# 18650_Capacity.net
KiCad netlist of a schematic drawn in EAGLE
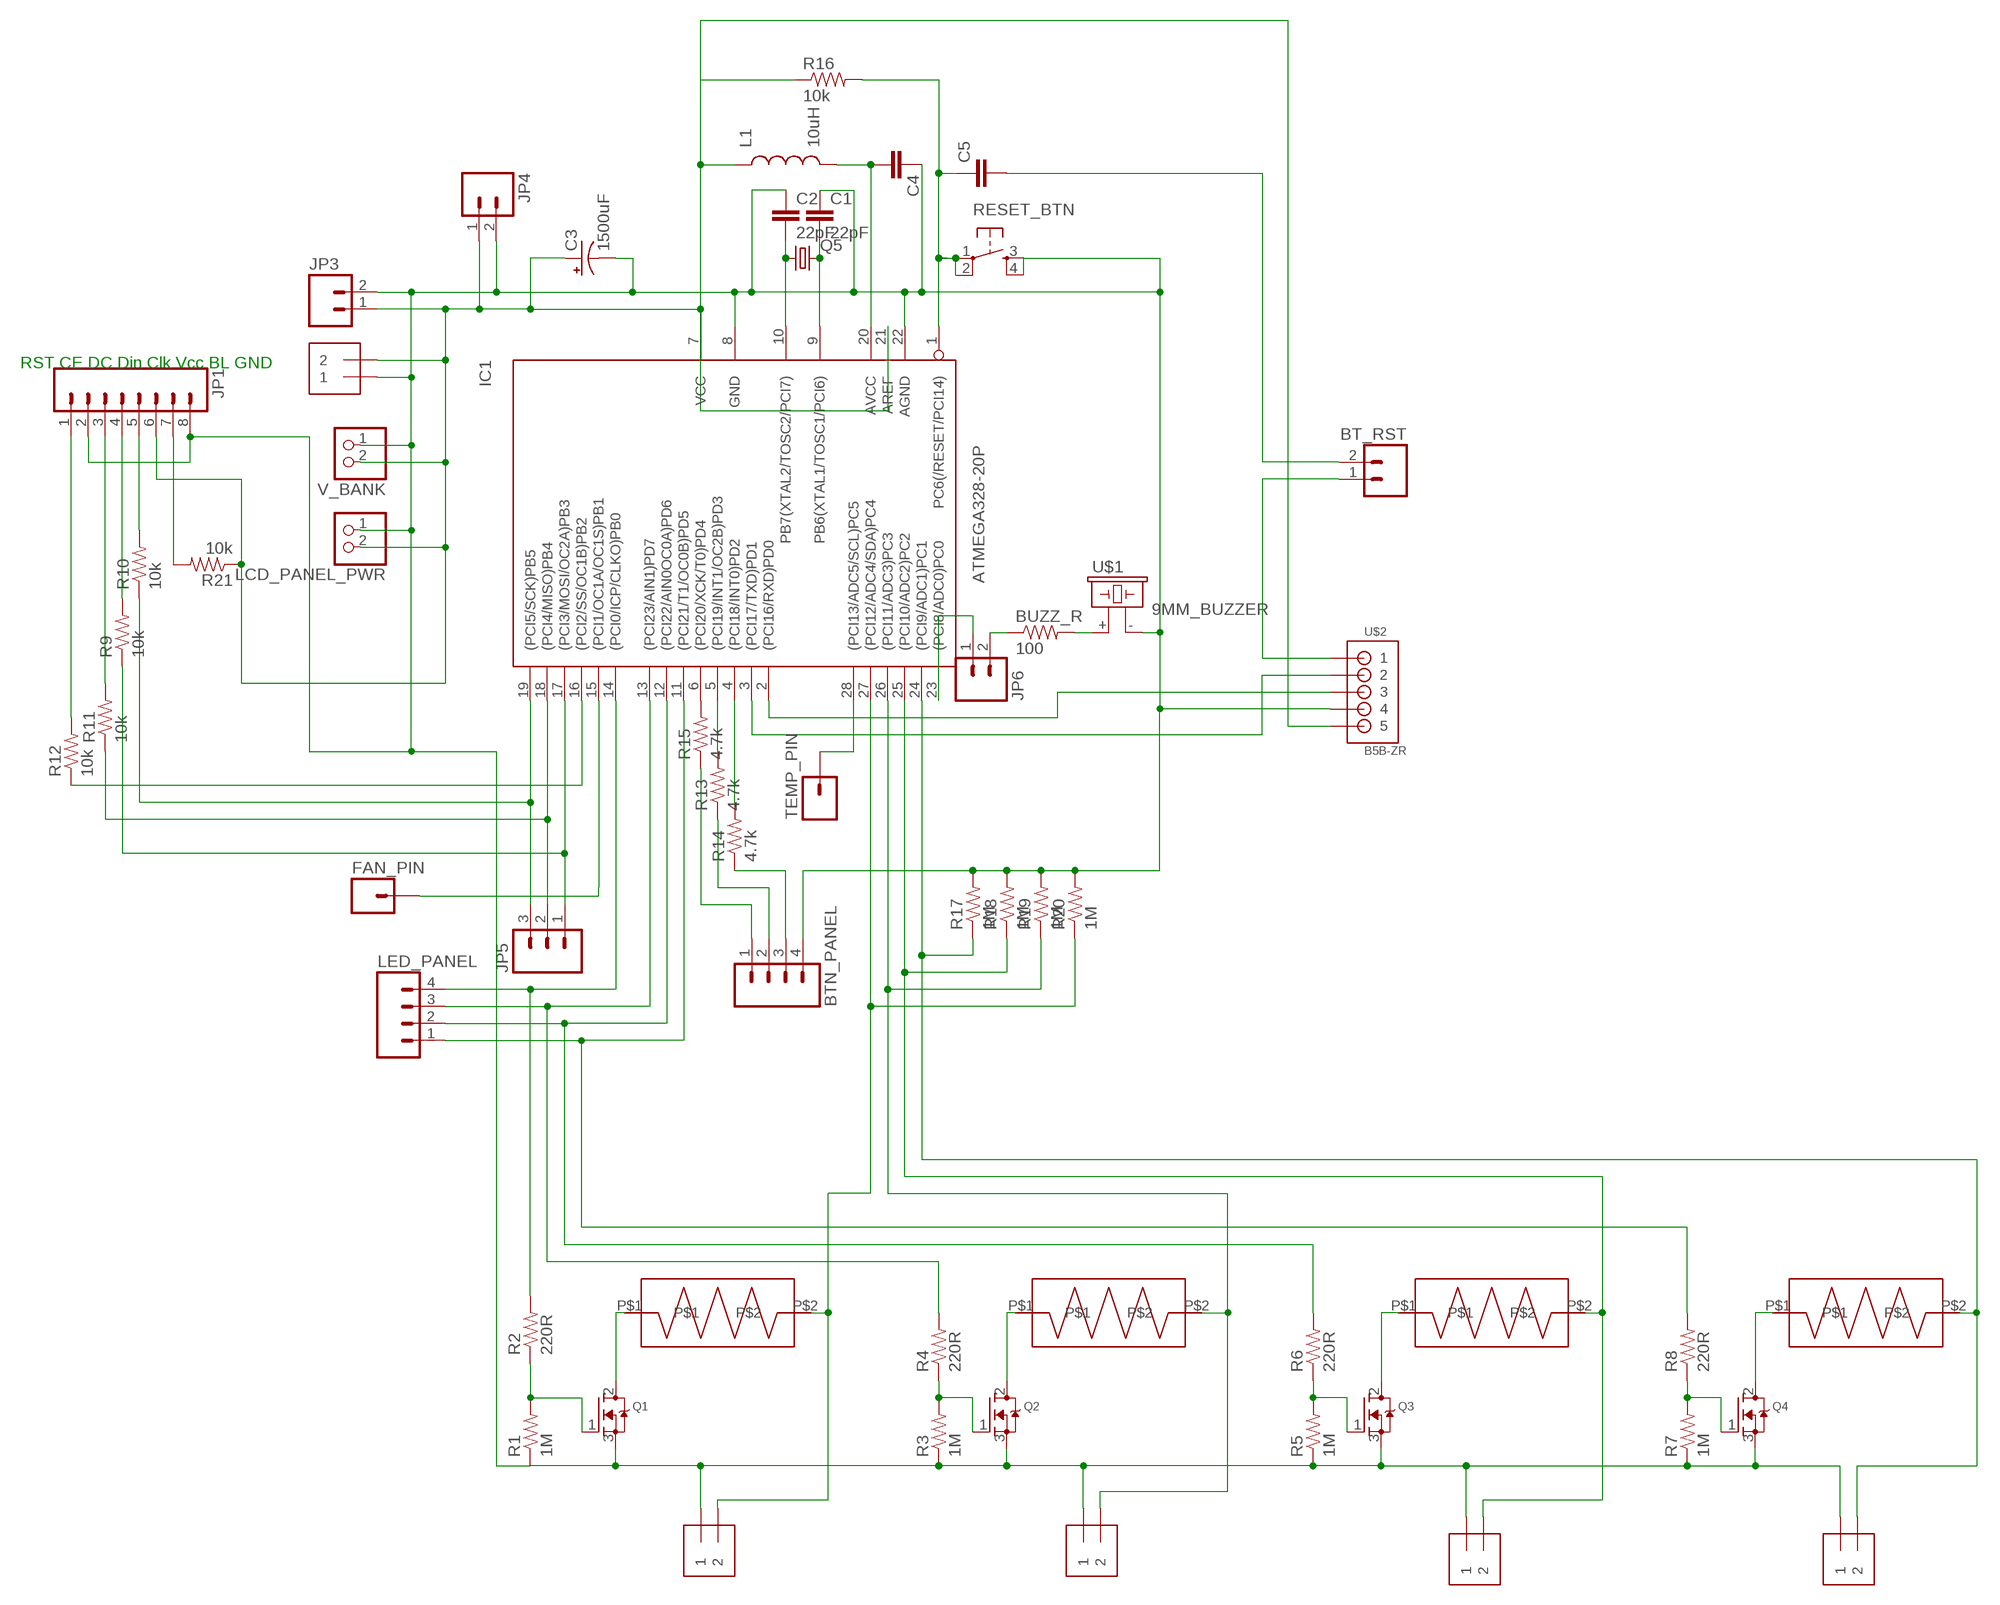
[diagram p0: schematic, sheet 1]

(export (version "E")
  (design (tool "Eeschema 10.0.6"))
  (components
    (comp (ref "5V_VIN")
      (value "1X2-3.5MM")
      (footprint "eagle-import:1X2-3.5MM")
      (libsource (lib "eagle-import") (part "1X2-3.5MM"))
    )
    (comp (ref "BATT1")
      (value "1X2-3.5MM")
      (footprint "eagle-import:1X2-3.5MM")
      (libsource (lib "eagle-import") (part "1X2-3.5MM"))
    )
    (comp (ref "BATT2")
      (value "1X2-3.5MM")
      (footprint "eagle-import:1X2-3.5MM")
      (libsource (lib "eagle-import") (part "1X2-3.5MM"))
    )
    (comp (ref "BATT3")
      (value "1X2-3.5MM")
      (footprint "eagle-import:1X2-3.5MM")
      (libsource (lib "eagle-import") (part "1X2-3.5MM"))
    )
    (comp (ref "BATT4")
      (value "1X2-3.5MM")
      (footprint "eagle-import:1X2-3.5MM")
      (libsource (lib "eagle-import") (part "1X2-3.5MM"))
    )
    (comp (ref "BTN_PANEL")
      (value "M04LOCK")
      (footprint "eagle-import:1X04_LOCK")
      (libsource (lib "eagle-import") (part "M04LOCK"))
    )
    (comp (ref "BT_RST")
      (value "M02LOCK")
      (footprint "eagle-import:1X02_LOCK")
      (libsource (lib "eagle-import") (part "M02LOCK"))
    )
    (comp (ref "BUZZ_R")
      (value "100")
      (footprint "eagle-import:1206")
      (libsource (lib "eagle-import") (part "SparkFun-Resistors_RESISTOR1206"))
    )
    (comp (ref "C1")
      (value "22pF")
      (footprint "eagle-import:CAP-PTH-SMALLEZ")
      (libsource (lib "eagle-import") (part "CAPEZ"))
    )
    (comp (ref "C2")
      (value "22pF")
      (footprint "eagle-import:CAP-PTH-SMALLEZ")
      (libsource (lib "eagle-import") (part "CAPEZ"))
    )
    (comp (ref "C3")
      (value "1500uF")
      (footprint "eagle-import:CPOL-RADIAL-100UF-25V")
      (libsource (lib "eagle-import") (part "CAP_POLPTH1"))
    )
    (comp (ref "C4")
      (value "CAPPTH1")
      (footprint "eagle-import:CAP-PTH-5MM")
      (libsource (lib "eagle-import") (part "CAPPTH1"))
    )
    (comp (ref "C5")
      (value "CAP_")
      (footprint "eagle-import:AXIAL-5MM")
      (libsource (lib "eagle-import") (part "CAP_"))
    )
    (comp (ref "FAN_PIN")
      (value "M01PTH")
      (footprint "eagle-import:1X01")
      (libsource (lib "eagle-import") (part "M01PTH"))
    )
    (comp (ref "IC1")
      (value "ATMEGA328-20P")
      (footprint "eagle-import:DIL28-3")
      (libsource (lib "eagle-import") (part "ATMEGA328P-20"))
    )
    (comp (ref "JP1")
      (value "M08LOCK")
      (footprint "eagle-import:1X08_LOCK")
      (libsource (lib "eagle-import") (part "M08LOCK"))
    )
    (comp (ref "JP3")
      (value "M02LOCK")
      (footprint "eagle-import:1X02_LOCK")
      (libsource (lib "eagle-import") (part "M02LOCK"))
    )
    (comp (ref "JP4")
      (value "M02LOCK")
      (footprint "eagle-import:1X02_LOCK")
      (libsource (lib "eagle-import") (part "M02LOCK"))
    )
    (comp (ref "JP5")
      (value "M03PTH")
      (footprint "eagle-import:1X03")
      (libsource (lib "eagle-import") (part "M03PTH"))
    )
    (comp (ref "JP6")
      (value "M02LOCK")
      (footprint "eagle-import:1X02_LOCK")
      (libsource (lib "eagle-import") (part "M02LOCK"))
    )
    (comp (ref "L1")
      (value "10uH")
      (footprint "eagle-import:RLB0912")
      (libsource (lib "eagle-import") (part "INDUCTORRLB0912"))
    )
    (comp (ref "LCD_PANEL_PWR")
      (value "JST_2PIN-THM")
      (footprint "eagle-import:JST-PH-2-THM")
      (libsource (lib "eagle-import") (part "JST_2PIN-THM"))
    )
    (comp (ref "LED_PANEL")
      (value "M04LOCK")
      (footprint "eagle-import:1X04_LOCK")
      (libsource (lib "eagle-import") (part "M04LOCK"))
    )
    (comp (ref "LOAD4")
      (value "CEMENT_RESISTOR")
      (footprint "eagle-import:CEMENT_RESISTOR")
      (libsource (lib "eagle-import") (part "CEMENT_RESISTOR"))
    )
    (comp (ref "LOAD_1")
      (value "CEMENT_RESISTOR")
      (footprint "eagle-import:CEMENT_RESISTOR")
      (libsource (lib "eagle-import") (part "CEMENT_RESISTOR"))
    )
    (comp (ref "LOAD_2")
      (value "CEMENT_RESISTOR")
      (footprint "eagle-import:CEMENT_RESISTOR")
      (libsource (lib "eagle-import") (part "CEMENT_RESISTOR"))
    )
    (comp (ref "Q1")
      (value "MOSFET-NGDS_TO220V")
      (footprint "eagle-import:TO220V")
      (libsource (lib "eagle-import") (part "MOSFET-NGDS_TO220V"))
    )
    (comp (ref "Q2")
      (value "MOSFET-NGDS_TO220V")
      (footprint "eagle-import:TO220V")
      (libsource (lib "eagle-import") (part "MOSFET-NGDS_TO220V"))
    )
    (comp (ref "Q3")
      (value "MOSFET-NGDS_TO220V")
      (footprint "eagle-import:TO220V")
      (libsource (lib "eagle-import") (part "MOSFET-NGDS_TO220V"))
    )
    (comp (ref "Q4")
      (value "MOSFET-NGDS_TO220V")
      (footprint "eagle-import:TO220V")
      (libsource (lib "eagle-import") (part "MOSFET-NGDS_TO220V"))
    )
    (comp (ref "Q5")
      (value "CRYTALHC49S")
      (footprint "eagle-import:HC49_S")
      (libsource (lib "eagle-import") (part "CRYTALHC49S"))
    )
    (comp (ref "R1")
      (value "1M")
      (footprint "eagle-import:AXIAL-0.3")
      (libsource (lib "eagle-import") (part "RESISTORAXIAL-0.3"))
    )
    (comp (ref "R2")
      (value "220R")
      (footprint "eagle-import:AXIAL-0.3")
      (libsource (lib "eagle-import") (part "RESISTORAXIAL-0.3"))
    )
    (comp (ref "R3")
      (value "1M")
      (footprint "eagle-import:AXIAL-0.3")
      (libsource (lib "eagle-import") (part "RESISTORAXIAL-0.3"))
    )
    (comp (ref "R4")
      (value "220R")
      (footprint "eagle-import:AXIAL-0.3")
      (libsource (lib "eagle-import") (part "RESISTORAXIAL-0.3"))
    )
    (comp (ref "R5")
      (value "1M")
      (footprint "eagle-import:AXIAL-0.3")
      (libsource (lib "eagle-import") (part "RESISTORAXIAL-0.3"))
    )
    (comp (ref "R6")
      (value "220R")
      (footprint "eagle-import:AXIAL-0.3")
      (libsource (lib "eagle-import") (part "RESISTORAXIAL-0.3"))
    )
    (comp (ref "R7")
      (value "1M")
      (footprint "eagle-import:AXIAL-0.3")
      (libsource (lib "eagle-import") (part "RESISTORAXIAL-0.3"))
    )
    (comp (ref "R8")
      (value "220R")
      (footprint "eagle-import:AXIAL-0.3")
      (libsource (lib "eagle-import") (part "RESISTORAXIAL-0.3"))
    )
    (comp (ref "R9")
      (value "10k")
      (footprint "eagle-import:AXIAL-0.3")
      (libsource (lib "eagle-import") (part "SparkFun-Resistors_RESISTORAXIAL-0.3"))
    )
    (comp (ref "R10")
      (value "10k")
      (footprint "eagle-import:AXIAL-0.3")
      (libsource (lib "eagle-import") (part "SparkFun-Resistors_RESISTORAXIAL-0.3"))
    )
    (comp (ref "R11")
      (value "10k")
      (footprint "eagle-import:AXIAL-0.3")
      (libsource (lib "eagle-import") (part "SparkFun-Resistors_RESISTORAXIAL-0.3"))
    )
    (comp (ref "R12")
      (value "10k")
      (footprint "eagle-import:AXIAL-0.3")
      (libsource (lib "eagle-import") (part "SparkFun-Resistors_RESISTORAXIAL-0.3"))
    )
    (comp (ref "R13")
      (value "4.7k")
      (footprint "eagle-import:AXIAL-0.3")
      (libsource (lib "eagle-import") (part "SparkFun-Resistors_RESISTORAXIAL-0.3"))
    )
    (comp (ref "R14")
      (value "4.7k")
      (footprint "eagle-import:AXIAL-0.3")
      (libsource (lib "eagle-import") (part "SparkFun-Resistors_RESISTORAXIAL-0.3"))
    )
    (comp (ref "R15")
      (value "4.7k")
      (footprint "eagle-import:AXIAL-0.3")
      (libsource (lib "eagle-import") (part "SparkFun-Resistors_RESISTORAXIAL-0.3"))
    )
    (comp (ref "R16")
      (value "10k")
      (footprint "eagle-import:AXIAL-0.3")
      (libsource (lib "eagle-import") (part "SparkFun-Resistors_RESISTORAXIAL-0.3"))
    )
    (comp (ref "R17")
      (value "1M")
      (footprint "eagle-import:0805")
      (libsource (lib "eagle-import") (part "RESISTOR0805-RES"))
    )
    (comp (ref "R18")
      (value "1M")
      (footprint "eagle-import:0805")
      (libsource (lib "eagle-import") (part "RESISTOR0805-RES"))
    )
    (comp (ref "R19")
      (value "1M")
      (footprint "eagle-import:0805")
      (libsource (lib "eagle-import") (part "RESISTOR0805-RES"))
    )
    (comp (ref "R20")
      (value "1M")
      (footprint "eagle-import:0805")
      (libsource (lib "eagle-import") (part "RESISTOR0805-RES"))
    )
    (comp (ref "R21")
      (value "10k")
      (footprint "eagle-import:1206")
      (libsource (lib "eagle-import") (part "RESISTOR1206"))
    )
    (comp (ref "RESET_BTN")
      (value "TAC_SWITCHPTH")
      (footprint "eagle-import:TACTILE-PTH")
      (libsource (lib "eagle-import") (part "TAC_SWITCHPTH"))
    )
    (comp (ref "TEMP_PIN")
      (value "M01PTH")
      (footprint "eagle-import:1X01")
      (libsource (lib "eagle-import") (part "M01PTH"))
    )
    (comp (ref "U$1")
      (value "9MM_BUZZER")
      (footprint "eagle-import:AL11P")
      (libsource (lib "eagle-import") (part "9MM_BUZZER"))
    )
    (comp (ref "U$2")
      (value "B5B-ZR")
      (footprint "eagle-import:B5B-ZR")
      (libsource (lib "eagle-import") (part "B5B-ZR"))
    )
    (comp (ref "U$3")
      (value "CEMENT_RESISTOR")
      (footprint "eagle-import:CEMENT_RESISTOR")
      (libsource (lib "eagle-import") (part "CEMENT_RESISTOR"))
    )
    (comp (ref "V_BANK")
      (value "JST_2PIN-THM")
      (footprint "eagle-import:JST-PH-2-THM")
      (libsource (lib "eagle-import") (part "JST_2PIN-THM"))
    )
  )
  (nets
    (net (code "1") (name "Net-(BT_RST-Pad1)") (class "Default")
      (node (ref "BT_RST") (pin "1") (pinfunction "1_1") (pintype "passive"))
      (node (ref "U$2") (pin "1") (pinfunction "1_1") (pintype "bidirectional"))
    )
    (net (code "2") (name "Net-(BUZZ_R-Pad1)") (class "Default")
      (node (ref "BUZZ_R") (pin "1") (pinfunction "1_1") (pintype "passive"))
      (node (ref "JP6") (pin "2") (pinfunction "2_2") (pintype "passive"))
    )
    (net (code "3") (name "Net-(C3-+)") (class "Default")
      (node (ref "5V_VIN") (pin "2") (pinfunction "2_2") (pintype "passive"))
      (node (ref "C3") (pin "1") (pinfunction "+_1") (pintype "passive"))
      (node (ref "IC1") (pin "21") (pinfunction "AREF_21") (pintype "bidirectional"))
      (node (ref "IC1") (pin "7") (pinfunction "VCC_7") (pintype "bidirectional"))
      (node (ref "JP1") (pin "6") (pinfunction "6_6") (pintype "passive"))
      (node (ref "JP3") (pin "1") (pinfunction "1_1") (pintype "passive"))
      (node (ref "JP4") (pin "1") (pinfunction "1_1") (pintype "passive"))
      (node (ref "L1") (pin "1") (pinfunction "1_1") (pintype "passive"))
      (node (ref "LCD_PANEL_PWR") (pin "2") (pinfunction "1_2") (pintype "passive"))
      (node (ref "R16") (pin "P$1") (pinfunction "1_P$1") (pintype "passive"))
      (node (ref "R21") (pin "1") (pinfunction "1_1") (pintype "passive"))
      (node (ref "U$2") (pin "5") (pinfunction "5_5") (pintype "bidirectional"))
      (node (ref "V_BANK") (pin "2") (pinfunction "1_2") (pintype "passive"))
    )
    (net (code "4") (name "Net-(C3--)") (class "Default")
      (node (ref "5V_VIN") (pin "1") (pinfunction "1_1") (pintype "passive"))
      (node (ref "BATT1") (pin "1") (pinfunction "1_1") (pintype "passive"))
      (node (ref "BATT2") (pin "1") (pinfunction "1_1") (pintype "passive"))
      (node (ref "BATT3") (pin "1") (pinfunction "1_1") (pintype "passive"))
      (node (ref "BATT4") (pin "1") (pinfunction "1_1") (pintype "passive"))
      (node (ref "BTN_PANEL") (pin "4") (pinfunction "4_4") (pintype "passive"))
      (node (ref "C1") (pin "1") (pinfunction "1_1") (pintype "passive"))
      (node (ref "C2") (pin "1") (pinfunction "1_1") (pintype "passive"))
      (node (ref "C3") (pin "2") (pinfunction "-_2") (pintype "passive"))
      (node (ref "C4") (pin "1") (pinfunction "1_1") (pintype "passive"))
      (node (ref "IC1") (pin "22") (pinfunction "AGND_22") (pintype "bidirectional"))
      (node (ref "IC1") (pin "8") (pinfunction "GND_8") (pintype "bidirectional"))
      (node (ref "JP1") (pin "2") (pinfunction "2_2") (pintype "passive"))
      (node (ref "JP1") (pin "8") (pinfunction "8_8") (pintype "passive"))
      (node (ref "JP3") (pin "2") (pinfunction "2_2") (pintype "passive"))
      (node (ref "JP4") (pin "2") (pinfunction "2_2") (pintype "passive"))
      (node (ref "LCD_PANEL_PWR") (pin "1") (pinfunction "2_1") (pintype "passive"))
      (node (ref "Q1") (pin "3") (pinfunction "S_3") (pintype "bidirectional"))
      (node (ref "Q2") (pin "3") (pinfunction "S_3") (pintype "bidirectional"))
      (node (ref "Q3") (pin "3") (pinfunction "S_3") (pintype "bidirectional"))
      (node (ref "Q4") (pin "3") (pinfunction "S_3") (pintype "bidirectional"))
      (node (ref "R1") (pin "P$1") (pinfunction "1_P$1") (pintype "passive"))
      (node (ref "R17") (pin "2") (pinfunction "2_2") (pintype "passive"))
      (node (ref "R18") (pin "2") (pinfunction "2_2") (pintype "passive"))
      (node (ref "R19") (pin "2") (pinfunction "2_2") (pintype "passive"))
      (node (ref "R20") (pin "2") (pinfunction "2_2") (pintype "passive"))
      (node (ref "R3") (pin "P$1") (pinfunction "1_P$1") (pintype "passive"))
      (node (ref "R5") (pin "P$1") (pinfunction "1_P$1") (pintype "passive"))
      (node (ref "R7") (pin "P$1") (pinfunction "1_P$1") (pintype "passive"))
      (node (ref "RESET_BTN") (pin "3") (pinfunction "3_3") (pintype "passive"))
      (node (ref "RESET_BTN") (pin "4") (pinfunction "4_4") (pintype "passive"))
      (node (ref "U$1") (pin "-") (pinfunction "2_-") (pintype "passive"))
      (node (ref "U$2") (pin "4") (pinfunction "4_4") (pintype "bidirectional"))
      (node (ref "V_BANK") (pin "1") (pinfunction "2_1") (pintype "passive"))
    )
    (net (code "5") (name "Net-(C5-1)") (class "Default")
      (node (ref "C5") (pin "P$1") (pinfunction "1_P$1") (pintype "passive"))
      (node (ref "IC1") (pin "1") (pinfunction "PC6(/RESET/PCI14)_1") (pintype "bidirectional"))
      (node (ref "R16") (pin "P$2") (pinfunction "2_P$2") (pintype "passive"))
      (node (ref "RESET_BTN") (pin "1") (pinfunction "1_1") (pintype "passive"))
      (node (ref "RESET_BTN") (pin "2") (pinfunction "2_2") (pintype "passive"))
    )
    (net (code "6") (name "Net-(C5-2)") (class "Default")
      (node (ref "BT_RST") (pin "2") (pinfunction "2_2") (pintype "passive"))
      (node (ref "C5") (pin "P$2") (pinfunction "2_P$2") (pintype "passive"))
    )
    (net (code "7") (name "Net-(IC1-(PCI0{slash}ICP{slash}CLKO)PB0)") (class "Default")
      (node (ref "IC1") (pin "14") (pinfunction "(PCI0/ICP/CLKO)PB0_14") (pintype "bidirectional"))
      (node (ref "LED_PANEL") (pin "4") (pinfunction "4_4") (pintype "passive"))
      (node (ref "R2") (pin "P$2") (pinfunction "2_P$2") (pintype "passive"))
    )
    (net (code "8") (name "Net-(IC1-(PCI1{slash}OC1A{slash}OC1S)PB1)") (class "Default")
      (node (ref "FAN_PIN") (pin "1") (pinfunction "1_1") (pintype "passive"))
      (node (ref "IC1") (pin "15") (pinfunction "(PCI1/OC1A/OC1S)PB1_15") (pintype "bidirectional"))
    )
    (net (code "9") (name "Net-(IC1-(PCI2{slash}SS{slash}OC1B)PB2)") (class "Default")
      (node (ref "IC1") (pin "16") (pinfunction "(PCI2/SS/OC1B)PB2_16") (pintype "bidirectional"))
      (node (ref "R12") (pin "P$1") (pinfunction "1_P$1") (pintype "passive"))
    )
    (net (code "10") (name "Net-(IC1-(PCI3{slash}MOSI{slash}OC2A)PB3)") (class "Default")
      (node (ref "IC1") (pin "17") (pinfunction "(PCI3/MOSI/OC2A)PB3_17") (pintype "bidirectional"))
      (node (ref "JP5") (pin "1") (pinfunction "1_1") (pintype "passive"))
      (node (ref "R9") (pin "P$1") (pinfunction "1_P$1") (pintype "passive"))
    )
    (net (code "11") (name "Net-(IC1-(PCI4{slash}MISO)PB4)") (class "Default")
      (node (ref "IC1") (pin "18") (pinfunction "(PCI4/MISO)PB4_18") (pintype "bidirectional"))
      (node (ref "JP5") (pin "2") (pinfunction "2_2") (pintype "passive"))
      (node (ref "R11") (pin "P$1") (pinfunction "1_P$1") (pintype "passive"))
    )
    (net (code "12") (name "Net-(IC1-(PCI5{slash}SCK)PB5)") (class "Default")
      (node (ref "IC1") (pin "19") (pinfunction "(PCI5/SCK)PB5_19") (pintype "bidirectional"))
      (node (ref "JP5") (pin "3") (pinfunction "3_3") (pintype "passive"))
      (node (ref "R10") (pin "P$1") (pinfunction "1_P$1") (pintype "passive"))
    )
    (net (code "13") (name "Net-(IC1-(PCI8{slash}ADC0)PC0)") (class "Default")
      (node (ref "IC1") (pin "23") (pinfunction "(PCI8/ADC0)PC0_23") (pintype "bidirectional"))
      (node (ref "JP6") (pin "1") (pinfunction "1_1") (pintype "passive"))
    )
    (net (code "14") (name "Net-(IC1-(PCI9{slash}ADC1)PC1)") (class "Default")
      (node (ref "BATT4") (pin "2") (pinfunction "2_2") (pintype "passive"))
      (node (ref "IC1") (pin "24") (pinfunction "(PCI9/ADC1)PC1_24") (pintype "bidirectional"))
      (node (ref "LOAD4") (pin "P$2") (pinfunction "P$2_P$2") (pintype "bidirectional"))
      (node (ref "R17") (pin "1") (pinfunction "1_1") (pintype "passive"))
    )
    (net (code "15") (name "Net-(IC1-(PCI10{slash}ADC2)PC2)") (class "Default")
      (node (ref "BATT3") (pin "2") (pinfunction "2_2") (pintype "passive"))
      (node (ref "IC1") (pin "25") (pinfunction "(PCI10/ADC2)PC2_25") (pintype "bidirectional"))
      (node (ref "R18") (pin "1") (pinfunction "1_1") (pintype "passive"))
      (node (ref "U$3") (pin "P$2") (pinfunction "P$2_P$2") (pintype "bidirectional"))
    )
    (net (code "16") (name "Net-(IC1-(PCI11{slash}ADC3)PC3)") (class "Default")
      (node (ref "BATT2") (pin "2") (pinfunction "2_2") (pintype "passive"))
      (node (ref "IC1") (pin "26") (pinfunction "(PCI11/ADC3)PC3_26") (pintype "bidirectional"))
      (node (ref "LOAD_2") (pin "P$2") (pinfunction "P$2_P$2") (pintype "bidirectional"))
      (node (ref "R19") (pin "1") (pinfunction "1_1") (pintype "passive"))
    )
    (net (code "17") (name "Net-(IC1-(PCI12{slash}ADC4{slash}SDA)PC4)") (class "Default")
      (node (ref "BATT1") (pin "2") (pinfunction "2_2") (pintype "passive"))
      (node (ref "IC1") (pin "27") (pinfunction "(PCI12/ADC4/SDA)PC4_27") (pintype "bidirectional"))
      (node (ref "LOAD_1") (pin "P$2") (pinfunction "P$2_P$2") (pintype "bidirectional"))
      (node (ref "R20") (pin "1") (pinfunction "1_1") (pintype "passive"))
    )
    (net (code "18") (name "Net-(IC1-(PCI13{slash}ADC5{slash}SCL)PC5)") (class "Default")
      (node (ref "IC1") (pin "28") (pinfunction "(PCI13/ADC5/SCL)PC5_28") (pintype "bidirectional"))
      (node (ref "TEMP_PIN") (pin "1") (pinfunction "1_1") (pintype "passive"))
    )
    (net (code "19") (name "Net-(IC1-(PCI16{slash}RXD)PD0)") (class "Default")
      (node (ref "IC1") (pin "2") (pinfunction "(PCI16/RXD)PD0_2") (pintype "bidirectional"))
      (node (ref "U$2") (pin "3") (pinfunction "3_3") (pintype "bidirectional"))
    )
    (net (code "20") (name "Net-(IC1-(PCI17{slash}TXD)PD1)") (class "Default")
      (node (ref "IC1") (pin "3") (pinfunction "(PCI17/TXD)PD1_3") (pintype "bidirectional"))
      (node (ref "U$2") (pin "2") (pinfunction "2_2") (pintype "bidirectional"))
    )
    (net (code "21") (name "Net-(IC1-(PCI18{slash}INT0)PD2)") (class "Default")
      (node (ref "IC1") (pin "4") (pinfunction "(PCI18/INT0)PD2_4") (pintype "bidirectional"))
      (node (ref "R14") (pin "P$2") (pinfunction "2_P$2") (pintype "passive"))
    )
    (net (code "22") (name "Net-(IC1-(PCI19{slash}INT1{slash}OC2B)PD3)") (class "Default")
      (node (ref "IC1") (pin "5") (pinfunction "(PCI19/INT1/OC2B)PD3_5") (pintype "bidirectional"))
      (node (ref "R13") (pin "P$2") (pinfunction "2_P$2") (pintype "passive"))
    )
    (net (code "23") (name "Net-(IC1-(PCI20{slash}XCK{slash}T0)PD4)") (class "Default")
      (node (ref "IC1") (pin "6") (pinfunction "(PCI20/XCK/T0)PD4_6") (pintype "bidirectional"))
      (node (ref "R15") (pin "P$2") (pinfunction "2_P$2") (pintype "passive"))
    )
    (net (code "24") (name "Net-(IC1-(PCI21{slash}T1{slash}OC0B)PD5)") (class "Default")
      (node (ref "IC1") (pin "11") (pinfunction "(PCI21/T1/OC0B)PD5_11") (pintype "bidirectional"))
      (node (ref "LED_PANEL") (pin "1") (pinfunction "1_1") (pintype "passive"))
      (node (ref "R8") (pin "P$2") (pinfunction "2_P$2") (pintype "passive"))
    )
    (net (code "25") (name "Net-(IC1-(PCI22{slash}AIN0OC0A)PD6)") (class "Default")
      (node (ref "IC1") (pin "12") (pinfunction "(PCI22/AIN0OC0A)PD6_12") (pintype "bidirectional"))
      (node (ref "LED_PANEL") (pin "2") (pinfunction "2_2") (pintype "passive"))
      (node (ref "R6") (pin "P$2") (pinfunction "2_P$2") (pintype "passive"))
    )
    (net (code "26") (name "Net-(IC1-(PCI23{slash}AIN1)PD7)") (class "Default")
      (node (ref "IC1") (pin "13") (pinfunction "(PCI23/AIN1)PD7_13") (pintype "bidirectional"))
      (node (ref "LED_PANEL") (pin "3") (pinfunction "3_3") (pintype "passive"))
      (node (ref "R4") (pin "P$2") (pinfunction "2_P$2") (pintype "passive"))
    )
    (net (code "27") (name "Net-(IC1-AVCC)") (class "Default")
      (node (ref "C4") (pin "2") (pinfunction "2_2") (pintype "passive"))
      (node (ref "IC1") (pin "20") (pinfunction "AVCC_20") (pintype "bidirectional"))
      (node (ref "L1") (pin "2") (pinfunction "2_2") (pintype "passive"))
    )
    (net (code "28") (name "Net-(IC1-PB6(XTAL1{slash}TOSC1{slash}PCI6))") (class "Default")
      (node (ref "C1") (pin "2") (pinfunction "2_2") (pintype "passive"))
      (node (ref "IC1") (pin "9") (pinfunction "PB6(XTAL1/TOSC1/PCI6)_9") (pintype "bidirectional"))
      (node (ref "Q5") (pin "2") (pinfunction "2_2") (pintype "passive"))
    )
    (net (code "29") (name "Net-(IC1-PB7(XTAL2{slash}TOSC2{slash}PCI7))") (class "Default")
      (node (ref "C2") (pin "2") (pinfunction "2_2") (pintype "passive"))
      (node (ref "IC1") (pin "10") (pinfunction "PB7(XTAL2/TOSC2/PCI7)_10") (pintype "bidirectional"))
      (node (ref "Q5") (pin "1") (pinfunction "1_1") (pintype "passive"))
    )
    (net (code "30") (name "Net-(JP1-Pad7)") (class "Default")
      (node (ref "JP1") (pin "7") (pinfunction "7_7") (pintype "passive"))
      (node (ref "R21") (pin "2") (pinfunction "2_2") (pintype "passive"))
    )
    (net (code "31") (name "Net-(Q1-D)") (class "Default")
      (node (ref "LOAD_1") (pin "P$1") (pinfunction "P$1_P$1") (pintype "bidirectional"))
      (node (ref "Q1") (pin "2") (pinfunction "D_2") (pintype "bidirectional"))
    )
    (net (code "32") (name "Net-(Q1-G)") (class "Default")
      (node (ref "Q1") (pin "1") (pinfunction "G_1") (pintype "bidirectional"))
      (node (ref "R1") (pin "P$2") (pinfunction "2_P$2") (pintype "passive"))
      (node (ref "R2") (pin "P$1") (pinfunction "1_P$1") (pintype "passive"))
    )
    (net (code "33") (name "Net-(Q2-D)") (class "Default")
      (node (ref "LOAD_2") (pin "P$1") (pinfunction "P$1_P$1") (pintype "bidirectional"))
      (node (ref "Q2") (pin "2") (pinfunction "D_2") (pintype "bidirectional"))
    )
    (net (code "34") (name "Net-(Q2-G)") (class "Default")
      (node (ref "Q2") (pin "1") (pinfunction "G_1") (pintype "bidirectional"))
      (node (ref "R3") (pin "P$2") (pinfunction "2_P$2") (pintype "passive"))
      (node (ref "R4") (pin "P$1") (pinfunction "1_P$1") (pintype "passive"))
    )
    (net (code "35") (name "Net-(Q3-D)") (class "Default")
      (node (ref "Q3") (pin "2") (pinfunction "D_2") (pintype "bidirectional"))
      (node (ref "U$3") (pin "P$1") (pinfunction "P$1_P$1") (pintype "bidirectional"))
    )
    (net (code "36") (name "Net-(Q3-G)") (class "Default")
      (node (ref "Q3") (pin "1") (pinfunction "G_1") (pintype "bidirectional"))
      (node (ref "R5") (pin "P$2") (pinfunction "2_P$2") (pintype "passive"))
      (node (ref "R6") (pin "P$1") (pinfunction "1_P$1") (pintype "passive"))
    )
    (net (code "37") (name "Net-(Q4-D)") (class "Default")
      (node (ref "LOAD4") (pin "P$1") (pinfunction "P$1_P$1") (pintype "bidirectional"))
      (node (ref "Q4") (pin "2") (pinfunction "D_2") (pintype "bidirectional"))
    )
    (net (code "38") (name "Net-(Q4-G)") (class "Default")
      (node (ref "Q4") (pin "1") (pinfunction "G_1") (pintype "bidirectional"))
      (node (ref "R7") (pin "P$2") (pinfunction "2_P$2") (pintype "passive"))
      (node (ref "R8") (pin "P$1") (pinfunction "1_P$1") (pintype "passive"))
    )
    (net (code "39") (name "Net-(R9-2)") (class "Default")
      (node (ref "JP1") (pin "4") (pinfunction "4_4") (pintype "passive"))
      (node (ref "R9") (pin "P$2") (pinfunction "2_P$2") (pintype "passive"))
    )
    (net (code "40") (name "Net-(R10-2)") (class "Default")
      (node (ref "JP1") (pin "5") (pinfunction "5_5") (pintype "passive"))
      (node (ref "R10") (pin "P$2") (pinfunction "2_P$2") (pintype "passive"))
    )
    (net (code "41") (name "Net-(R11-2)") (class "Default")
      (node (ref "JP1") (pin "3") (pinfunction "3_3") (pintype "passive"))
      (node (ref "R11") (pin "P$2") (pinfunction "2_P$2") (pintype "passive"))
    )
    (net (code "42") (name "Net-(R12-2)") (class "Default")
      (node (ref "JP1") (pin "1") (pinfunction "1_1") (pintype "passive"))
      (node (ref "R12") (pin "P$2") (pinfunction "2_P$2") (pintype "passive"))
    )
    (net (code "43") (name "Net-(R13-1)") (class "Default")
      (node (ref "BTN_PANEL") (pin "2") (pinfunction "2_2") (pintype "passive"))
      (node (ref "R13") (pin "P$1") (pinfunction "1_P$1") (pintype "passive"))
    )
    (net (code "44") (name "Net-(R14-1)") (class "Default")
      (node (ref "BTN_PANEL") (pin "3") (pinfunction "3_3") (pintype "passive"))
      (node (ref "R14") (pin "P$1") (pinfunction "1_P$1") (pintype "passive"))
    )
    (net (code "45") (name "Net-(R15-1)") (class "Default")
      (node (ref "BTN_PANEL") (pin "1") (pinfunction "1_1") (pintype "passive"))
      (node (ref "R15") (pin "P$1") (pinfunction "1_P$1") (pintype "passive"))
    )
    (net (code "46") (name "Net-(U$1-1)") (class "Default")
      (node (ref "BUZZ_R") (pin "2") (pinfunction "2_2") (pintype "passive"))
      (node (ref "U$1") (pin "+") (pinfunction "1_+") (pintype "passive"))
    )
  )
)
